# Power_Supply.net
KiCad netlist of a schematic drawn in Altium Designer
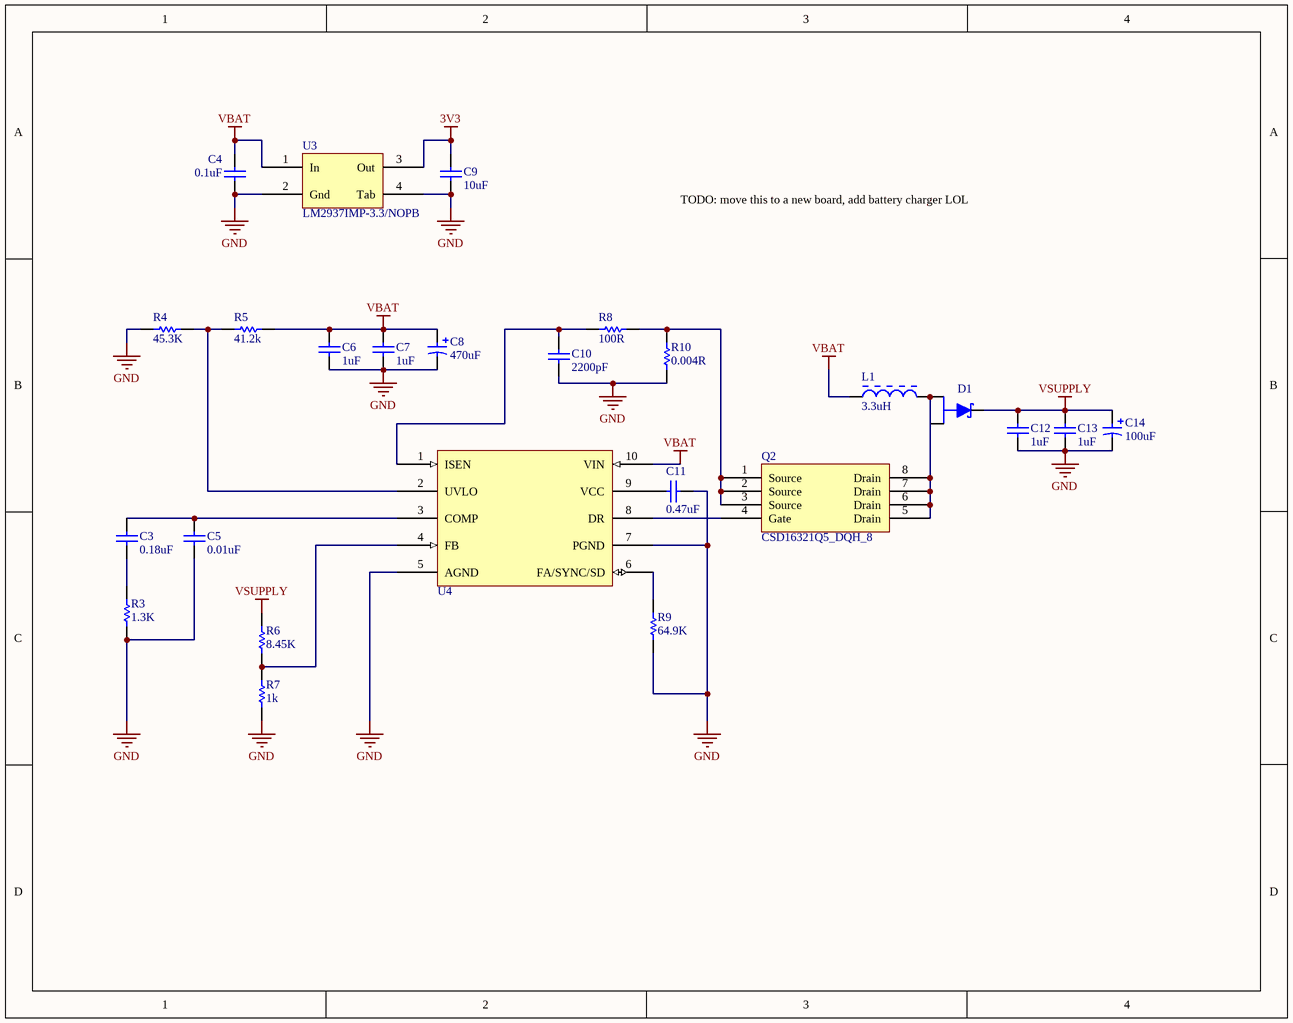
[diagram p0: Power_Supply.SchDoc]

(export (version "E")
  (design (tool "Eeschema 10.0.6"))
  (components
    (comp (ref "C3")
      (value "0.18uF")
      (footprint "CAPC1608X09N")
      (fields
        (field (name "DIGIKEY PART NUMBER") "490-6431-1-ND")
        (field (name "MANUFACTURER") "Murata")
        (field (name "VOLTAGE") "25V")
      )
      (libsource (lib "Speaker Library") (part "CAP CER 0.18uF 0603"))
    )
    (comp (ref "C4")
      (value "0.1uF")
      (footprint "CAPC1608X09N")
      (fields
        (field (name "DIGIKEY PART NUMBER") "490-3285-1-ND")
        (field (name "VOLTAGE") "100V")
        (field (name "TOLERANCE") "10%")
      )
      (libsource (lib "Speaker Library") (part "CAP CER 0.1uF 0603"))
    )
    (comp (ref "C5")
      (value "0.01uF")
      (footprint "CAPC1608X09N")
      (fields (field (name "DIGIKEY PART NUMBER") "490-9666-1-ND") (field (name "MANUFACTURER") "Murata"))
      (libsource (lib "Speaker Library") (part "CAP CER 0.01uF 0603"))
    )
    (comp (ref "C6")
      (value "1uF")
      (footprint "CAPC1608X09N")
      (fields (field (name "DIGIKEY PART NUMBER") "490-10487-1-ND") (field (name "VOLTAGE") "35V"))
      (libsource (lib "Speaker Library") (part "CAP CER 1uF 0603"))
    )
    (comp (ref "C7")
      (value "1uF")
      (footprint "CAPC1608X09N")
      (fields (field (name "DIGIKEY PART NUMBER") "490-10487-1-ND") (field (name "VOLTAGE") "35V"))
      (libsource (lib "Speaker Library") (part "CAP CER 1uF 0603"))
    )
    (comp (ref "C8")
      (value "470uF")
      (footprint "NICHICON 8x10 CAP")
      (fields (field (name "DIGIKEY PART NUMBER") "493-2181-1-ND"))
      (libsource (lib "Speaker Library") (part "CAP ALUM 470uF SMD"))
    )
    (comp (ref "C9")
      (value "10uF")
      (footprint "CAPC3216X18N")
      (description "3V3 filter cap")
      (fields (field (name "DIGIKEY PART NUMBER") "490-6518-1-ND") (field (name "VOLTAGE") "25V"))
      (libsource (lib "Speaker Library") (part "CAP CER 10uF 1206"))
    )
    (comp (ref "C10")
      (value "2200pF")
      (footprint "CAPC1608X09N")
      (fields
        (field (name "DIGIKEY PART NUMBER") "490-7768-1-ND")
        (field (name "MANUFACTURER") "Murata")
        (field (name "VOLTAGE") "50V")
      )
      (libsource (lib "Speaker Library") (part "CAP CER 2200pF 0603"))
    )
    (comp (ref "C11")
      (value "0.47uF")
      (footprint "CAPC1608X09N")
      (fields (field (name "DIGIKEY PART NUMBER") "490-3291-1-ND") (field (name "VOLTAGE") "25V"))
      (libsource (lib "Speaker Library") (part "CAP CER 0.47uF 0603"))
    )
    (comp (ref "C12")
      (value "1uF")
      (footprint "CAPC1608X09N")
      (fields (field (name "DIGIKEY PART NUMBER") "490-10487-1-ND") (field (name "VOLTAGE") "35V"))
      (libsource (lib "Speaker Library") (part "CAP CER 1uF 0603"))
    )
    (comp (ref "C13")
      (value "1uF")
      (footprint "CAPC1608X09N")
      (fields (field (name "DIGIKEY PART NUMBER") "490-10487-1-ND") (field (name "VOLTAGE") "35V"))
      (libsource (lib "Speaker Library") (part "CAP CER 1uF 0603"))
    )
    (comp (ref "C14")
      (value "100uF")
      (footprint "PCAP_8x10-ELEC00")
      (fields
        (field (name "DIGIKEY PART NUMBER") "493-2226-1-ND")
        (field (name "MANUFACTURER") "Nichicon")
        (field (name "VOLTAGE") "50V")
      )
      (libsource (lib "Speaker Library") (part "CAP ALUM 100uF SMD"))
    )
    (comp (ref "D1")
      (value "~")
      (footprint "ONSEMI DPAK-3")
      (description "SHOTTKEY 35V 8A")
      (fields (field (name "VOLTAGE") "35V") (field (name "DIGIKEY PART NUMBER") "MBRD835LT4GOSCT-ND"))
      (libsource (lib "Speaker Library") (part "MBRD835LT4G"))
    )
    (comp (ref "L1")
      (value "3.3uH")
      (footprint "IND_BOURNS_SRP00 - duplicate")
      (fields (field (name "DIGIKEY PART NUMBER") "SRP7030-3R3FMCT-ND"))
      (libsource (lib "Speaker Library") (part "IND 3.3µH 7A SMD"))
    )
    (comp (ref "Q2")
      (value "CSD16321Q5_DQH_8")
      (footprint "DQH8")
      (fields
        (field (name "MANUFACTURER") "Texas Instruments")
        (field (name "GENERIC_PART_NUMBER") "CSD16321Q5")
        (field (name "DIGIKEY PART NUMBER") "296-25643-1-ND")
      )
      (libsource (lib "Speaker Library") (part "CSD16321Q5_DQH_8"))
    )
    (comp (ref "R3")
      (value "1.3K")
      (footprint "RESC1608X06N")
      (fields
        (field (name "TOLERANCE") "1%")
        (field (name "POWER") "0.1W")
        (field (name "MANUFACTURER") "Vishay Dale")
      )
      (libsource (lib "Speaker Library") (part "RES 1.3K 0603"))
    )
    (comp (ref "R4")
      (value "45.3K")
      (footprint "RESC1608X06N")
      (fields
        (field (name "TOLERANCE") "1%")
        (field (name "POWER") "0.1W")
        (field (name "MANUFACTURER") "Vishay Dale")
      )
      (libsource (lib "Speaker Library") (part "RES 45.3K 0603"))
    )
    (comp (ref "R5")
      (value "41.2k")
      (footprint "RESC1608X06N")
      (fields
        (field (name "TOLERANCE") "1%")
        (field (name "POWER") "0.1W")
        (field (name "MANUFACTURER") "Vishay Dale")
      )
      (libsource (lib "Speaker Library") (part "RES 41.2K 0603"))
    )
    (comp (ref "R6")
      (value "8.45K")
      (footprint "RESC1608X06N")
      (fields
        (field (name "TOLERANCE") "1%")
        (field (name "POWER") "0.1W")
        (field (name "MANUFACTURER") "Vishay Dale")
      )
      (libsource (lib "Speaker Library") (part "RES 8.45K 0603"))
    )
    (comp (ref "R7")
      (value "1k")
      (footprint "RESC1608X06N")
      (fields
        (field (name "TOLERANCE") "1%")
        (field (name "POWER") "0.25W")
        (field (name "MANUFACTURER") "Panasonic")
      )
      (libsource (lib "Speaker Library") (part "RES 1K 0603"))
    )
    (comp (ref "R8")
      (value "100R")
      (footprint "RESC1608X06N")
      (fields
        (field (name "TOLERANCE") "1%")
        (field (name "POWER") "0.25W")
        (field (name "DIGIKEY PART NUMBER") "541-100SACT-ND")
      )
      (libsource (lib "Speaker Library") (part "RES 100R 0603"))
    )
    (comp (ref "R9")
      (value "64.9K")
      (footprint "RESC1608X06N")
      (fields
        (field (name "TOLERANCE") "1%")
        (field (name "POWER") "0.1W")
        (field (name "MANUFACTURER") "Vishay Dale")
      )
      (libsource (lib "Speaker Library") (part "RES 64.9K 0603"))
    )
    (comp (ref "R10")
      (value "0.004R")
      (footprint "RESC6533X09N")
      (fields
        (field (name "TOLERANCE") "1%")
        (field (name "POWER") "1W")
        (field (name "MANUFACTURER") "Panasonic")
      )
      (libsource (lib "Speaker Library") (part "RES 0.004R 2512"))
    )
    (comp (ref "U3")
      (value "LM2937IMP-3.3/NOPB")
      (footprint "DSO-G3/C6.4")
      (fields (field (name "DIGIKEY PART NUMBER") "LM2937IMP-3.3/NOPBCT-ND"))
      (libsource (lib "Speaker Library") (part "LM2937IMP-3.3/NOPB"))
    )
    (comp (ref "U4")
      (value "LM3481")
      (footprint "VSSOP10")
      (description "IC REG CTRLR MULT TOP 10MSOP")
      (fields (field (name "DIGIKEY PART NUMBER") "LM3481MM/NOPBCT-ND"))
      (libsource (lib "Speaker Library") (part "LM3481"))
    )
  )
  (nets
    (net (code "1") (name "3V3") (class "Default")
      (node (ref "C9") (pin "2") (pinfunction "2_2") (pintype "passive"))
      (node (ref "U3") (pin "3") (pinfunction "Out_3") (pintype "power_in"))
    )
    (net (code "2") (name "GND") (class "Default")
      (node (ref "C10") (pin "1") (pinfunction "1_1") (pintype "passive"))
      (node (ref "C11") (pin "2") (pinfunction "2_2") (pintype "passive"))
      (node (ref "C12") (pin "1") (pinfunction "1_1") (pintype "passive"))
      (node (ref "C13") (pin "1") (pinfunction "1_1") (pintype "passive"))
      (node (ref "C14") (pin "2") (pinfunction "2_2") (pintype "passive"))
      (node (ref "C4") (pin "1") (pinfunction "1_1") (pintype "passive"))
      (node (ref "C5") (pin "1") (pinfunction "1_1") (pintype "passive"))
      (node (ref "C6") (pin "1") (pinfunction "1_1") (pintype "passive"))
      (node (ref "C7") (pin "1") (pinfunction "1_1") (pintype "passive"))
      (node (ref "C8") (pin "2") (pinfunction "2_2") (pintype "passive"))
      (node (ref "C9") (pin "1") (pinfunction "1_1") (pintype "passive"))
      (node (ref "R10") (pin "1") (pinfunction "1_1") (pintype "passive"))
      (node (ref "R3") (pin "1") (pinfunction "1_1") (pintype "passive"))
      (node (ref "R4") (pin "1") (pinfunction "1_1") (pintype "passive"))
      (node (ref "R7") (pin "1") (pinfunction "1_1") (pintype "passive"))
      (node (ref "R9") (pin "1") (pinfunction "1_1") (pintype "passive"))
      (node (ref "U3") (pin "2") (pinfunction "Gnd_2") (pintype "power_in"))
      (node (ref "U3") (pin "4") (pinfunction "Tab_4") (pintype "power_in"))
      (node (ref "U4") (pin "5") (pinfunction "AGND_5") (pintype "power_in"))
      (node (ref "U4") (pin "7") (pinfunction "PGND_7") (pintype "power_in"))
    )
    (net (code "3") (name "Net-(C3-Pad1)") (class "Default")
      (node (ref "C3") (pin "1") (pinfunction "1_1") (pintype "passive"))
      (node (ref "R3") (pin "2") (pinfunction "2_2") (pintype "passive"))
    )
    (net (code "4") (name "Net-(D1-Pad1)") (class "Default")
      (node (ref "D1") (pin "1") (pinfunction "1_1") (pintype "passive"))
      (node (ref "L1") (pin "2") (pinfunction "2_2") (pintype "passive"))
      (node (ref "Q2") (pin "5") (pinfunction "Drain_5") (pintype "passive"))
      (node (ref "Q2") (pin "6") (pinfunction "Drain_6") (pintype "passive"))
      (node (ref "Q2") (pin "7") (pinfunction "Drain_7") (pintype "passive"))
      (node (ref "Q2") (pin "8") (pinfunction "Drain_8") (pintype "passive"))
    )
    (net (code "5") (name "Net-(Q2-Gate)") (class "Default")
      (node (ref "Q2") (pin "4") (pinfunction "Gate_4") (pintype "passive"))
      (node (ref "U4") (pin "8") (pinfunction "DR_8") (pintype "passive"))
    )
    (net (code "6") (name "Net-(Q2-Source-Pad1)") (class "Default")
      (node (ref "Q2") (pin "1") (pinfunction "Source_1") (pintype "passive"))
      (node (ref "Q2") (pin "2") (pinfunction "Source_2") (pintype "passive"))
      (node (ref "Q2") (pin "3") (pinfunction "Source_3") (pintype "passive"))
      (node (ref "R10") (pin "2") (pinfunction "2_2") (pintype "passive"))
      (node (ref "R8") (pin "2") (pinfunction "2_2") (pintype "passive"))
    )
    (net (code "7") (name "Net-(U4-COMP)") (class "Default")
      (node (ref "C3") (pin "2") (pinfunction "2_2") (pintype "passive"))
      (node (ref "C5") (pin "2") (pinfunction "2_2") (pintype "passive"))
      (node (ref "U4") (pin "3") (pinfunction "COMP_3") (pintype "passive"))
    )
    (net (code "8") (name "Net-(U4-FA{slash}SYNC{slash}SD)") (class "Default")
      (node (ref "R9") (pin "2") (pinfunction "2_2") (pintype "passive"))
      (node (ref "U4") (pin "6") (pinfunction "FA/SYNC/SD_6") (pintype "bidirectional"))
    )
    (net (code "9") (name "Net-(U4-FB)") (class "Default")
      (node (ref "R6") (pin "2") (pinfunction "2_2") (pintype "passive"))
      (node (ref "R7") (pin "2") (pinfunction "2_2") (pintype "passive"))
      (node (ref "U4") (pin "4") (pinfunction "FB_4") (pintype "input"))
    )
    (net (code "10") (name "Net-(U4-ISEN)") (class "Default")
      (node (ref "C10") (pin "2") (pinfunction "2_2") (pintype "passive"))
      (node (ref "R8") (pin "1") (pinfunction "1_1") (pintype "passive"))
      (node (ref "U4") (pin "1") (pinfunction "ISEN_1") (pintype "input"))
    )
    (net (code "11") (name "Net-(U4-UVLO)") (class "Default")
      (node (ref "R4") (pin "2") (pinfunction "2_2") (pintype "passive"))
      (node (ref "R5") (pin "1") (pinfunction "1_1") (pintype "passive"))
      (node (ref "U4") (pin "2") (pinfunction "UVLO_2") (pintype "passive"))
    )
    (net (code "12") (name "Net-(U4-VCC)") (class "Default")
      (node (ref "C11") (pin "1") (pinfunction "1_1") (pintype "passive"))
      (node (ref "U4") (pin "9") (pinfunction "VCC_9") (pintype "power_in"))
    )
    (net (code "13") (name "VBAT") (class "Default")
      (node (ref "C4") (pin "2") (pinfunction "2_2") (pintype "passive"))
      (node (ref "C6") (pin "2") (pinfunction "2_2") (pintype "passive"))
      (node (ref "C7") (pin "2") (pinfunction "2_2") (pintype "passive"))
      (node (ref "C8") (pin "1") (pinfunction "1_1") (pintype "passive"))
      (node (ref "L1") (pin "1") (pinfunction "1_1") (pintype "passive"))
      (node (ref "R5") (pin "2") (pinfunction "2_2") (pintype "passive"))
      (node (ref "U3") (pin "1") (pinfunction "In_1") (pintype "power_in"))
      (node (ref "U4") (pin "10") (pinfunction "VIN_10") (pintype "input"))
    )
    (net (code "14") (name "VSUPPLY") (class "Default")
      (node (ref "C12") (pin "2") (pinfunction "2_2") (pintype "passive"))
      (node (ref "C13") (pin "2") (pinfunction "2_2") (pintype "passive"))
      (node (ref "C14") (pin "1") (pinfunction "1_1") (pintype "passive"))
      (node (ref "D1") (pin "4") (pinfunction "4_4") (pintype "passive"))
      (node (ref "R6") (pin "1") (pinfunction "1_1") (pintype "passive"))
    )
    (net (code "15") (name "unconnected-(D1-Pad3)") (class "Default")
      (node (ref "D1") (pin "3") (pinfunction "3_3") (pintype "passive"))
    )
  )
)
